# power.net
KiCad netlist of a schematic drawn in Altium Designer
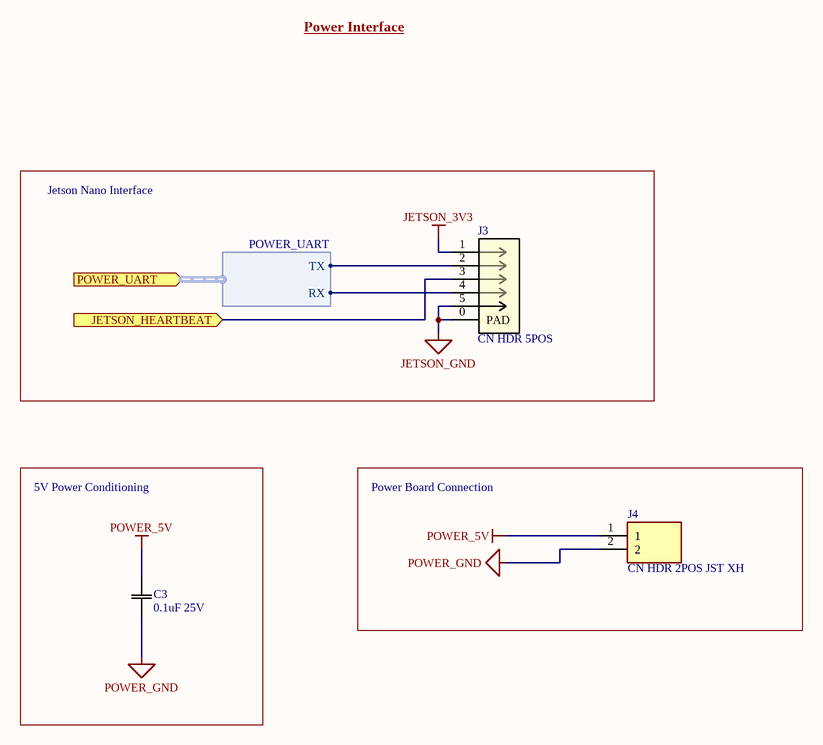
[diagram p0: power.SchDoc]

(export (version "E")
  (design (tool "Eeschema 10.0.6"))
  (components
    (comp (ref "C3")
      (value "0.1uF 25V")
      (footprint "0805")
      (description "Default Symbol for Capacitors")
      (fields (field (name "TOLERANCE") "10%") (field (name "PART NUMBER") "CAP 0.1uF 25V"))
      (libsource (lib "Capacitor_Library") (part "CAP_Default"))
    )
    (comp (ref "J3")
      (value "CN HDR 5POS")
      (footprint "CN HDR 5POS SMD 1.5MM")
      (description "Connector Header 5 Position")
      (libsource (lib "Connector_Library") (part "CN HDR 5POS"))
    )
    (comp (ref "J4")
      (value "CN HDR 2POS JST XH")
      (footprint "JST_B2B-XH-A(LF)(SN)")
      (description "Connector Header Through Hole 2 position 0.098 _2.50mm_\r\nJST XH")
      (fields (field (name "MP") "B2B-XH-A_LF__SN_") (field (name "MF") "JST Sales"))
      (libsource (lib "Connector_Library") (part "CN HDR 2POS JST XH"))
    )
  )
  (nets
    (net (code "2") (name "/JETSON_HEARTBEAT") (class "Default")
      (node (ref "J3") (pin "3") (pinfunction "3_3") (pintype "passive"))
    )
    (net (code "3") (name "/RX") (class "Default")
      (node (ref "J3") (pin "4") (pinfunction "4_4") (pintype "passive"))
    )
    (net (code "4") (name "/TX") (class "Default")
      (node (ref "J3") (pin "2") (pinfunction "2_2") (pintype "passive"))
    )
    (net (code "6") (name "JETSON_3V3") (class "Default")
      (node (ref "J3") (pin "1") (pinfunction "1_1") (pintype "passive"))
    )
    (net (code "7") (name "JETSON_GND") (class "Default")
      (node (ref "J3") (pin "0") (pinfunction "PAD_0") (pintype "passive"))
      (node (ref "J3") (pin "5") (pinfunction "5_5") (pintype "passive"))
    )
    (net (code "8") (name "POWER_5V") (class "Default")
      (node (ref "C3") (pin "2") (pinfunction "C2_2") (pintype "passive"))
      (node (ref "J4") (pin "1") (pinfunction "1_1") (pintype "passive"))
    )
    (net (code "9") (name "POWER_GND") (class "Default")
      (node (ref "C3") (pin "1") (pinfunction "C1_1") (pintype "passive"))
      (node (ref "J4") (pin "2") (pinfunction "2_2") (pintype "passive"))
    )
  )
)
